# genius_sch.net
KiCad netlist of a schematic drawn in Altium Designer
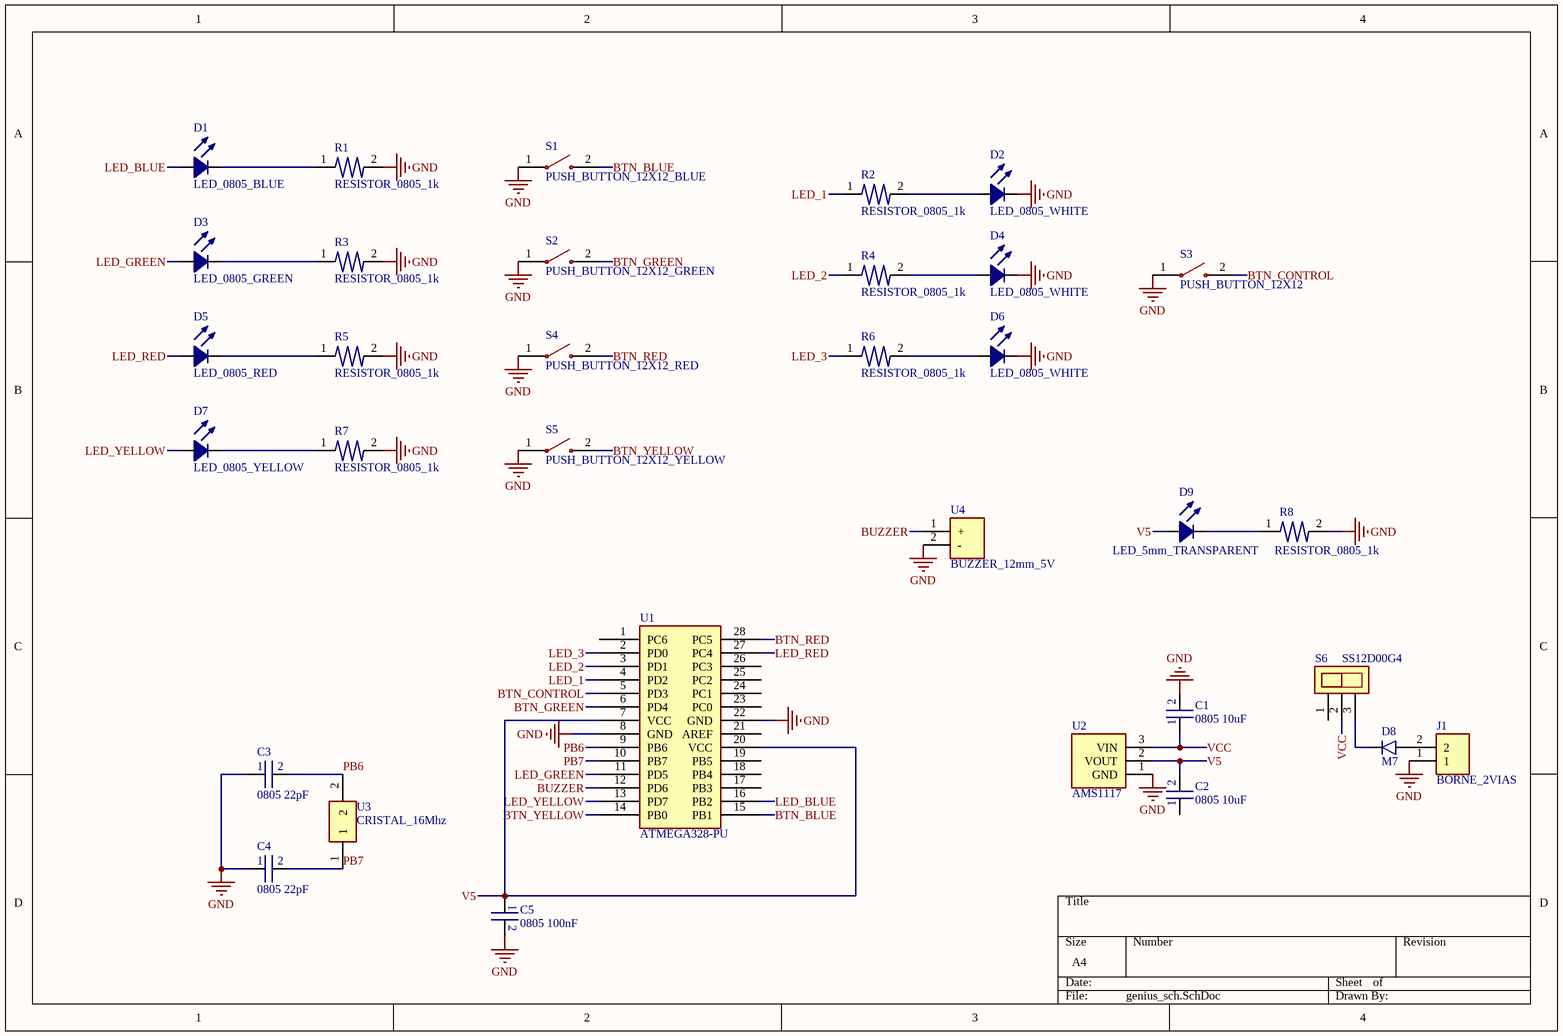
[diagram p0: genius_sch.SchDoc]

(export (version "E")
  (design (tool "Eeschema 10.0.6"))
  (components
    (comp (ref "C1")
      (value "0805 10uF")
      (footprint "CAPACITOR 0805")
      (libsource (lib "Capacitor Ceramico") (part "CAPACITOR 0805"))
    )
    (comp (ref "C2")
      (value "0805 10uF")
      (footprint "CAPACITOR 0805")
      (libsource (lib "Capacitor Ceramico") (part "CAPACITOR 0805"))
    )
    (comp (ref "C3")
      (value "0805 22pF")
      (footprint "CAPACITOR 0805")
      (libsource (lib "Capacitor Ceramico") (part "CAPACITOR 0805"))
    )
    (comp (ref "C4")
      (value "0805 22pF")
      (footprint "CAPACITOR 0805")
      (libsource (lib "Capacitor Ceramico") (part "CAPACITOR 0805"))
    )
    (comp (ref "C5")
      (value "0805 100nF")
      (footprint "CAPACITOR 0805")
      (libsource (lib "Capacitor Ceramico") (part "CAPACITOR 0805"))
    )
    (comp (ref "D1")
      (value "LED_0805_BLUE")
      (footprint "LED_0805_BLUE")
      (libsource (lib "LED") (part "LED_0805_BLUE"))
    )
    (comp (ref "D2")
      (value "LED_0805_WHITE")
      (footprint "LED_0805_WHITE")
      (libsource (lib "LED") (part "LED_0805_WHITE"))
    )
    (comp (ref "D3")
      (value "LED_0805_GREEN")
      (footprint "LED_0805_GREEN")
      (libsource (lib "LED") (part "LED_0805_GREEN"))
    )
    (comp (ref "D4")
      (value "LED_0805_WHITE")
      (footprint "LED_0805_WHITE")
      (libsource (lib "LED") (part "LED_0805_WHITE"))
    )
    (comp (ref "D5")
      (value "LED_0805_RED")
      (footprint "LED_0805_RED")
      (libsource (lib "LED") (part "LED_0805_RED"))
    )
    (comp (ref "D6")
      (value "LED_0805_WHITE")
      (footprint "LED_0805_WHITE")
      (libsource (lib "LED") (part "LED_0805_WHITE"))
    )
    (comp (ref "D7")
      (value "LED_0805_YELLOW")
      (footprint "LED_0805_YELLOW")
      (libsource (lib "LED") (part "LED_0805_YELLOW"))
    )
    (comp (ref "D8") (value "M7") (footprint "M7") (libsource (lib "Diode") (part "M7")))
    (comp (ref "D9")
      (value "LED_5mm_TRANSPARENT")
      (footprint "LED_5mm_TRANSPARENT")
      (libsource (lib "LED") (part "LED_5mm_TRANSPARENT"))
    )
    (comp (ref "J1")
      (value "BORNE_2VIAS")
      (footprint "BORNE_2VIAS")
      (libsource (lib "Connectors") (part "BORNE_2VIAS"))
    )
    (comp (ref "R1")
      (value "RESISTOR_0805_1k")
      (footprint "RESISTOR_0805_1k")
      (libsource (lib "Resistors") (part "RESISTOR_0805_1k"))
    )
    (comp (ref "R2")
      (value "RESISTOR_0805_1k")
      (footprint "RESISTOR_0805_1k")
      (libsource (lib "Resistors") (part "RESISTOR_0805_1k"))
    )
    (comp (ref "R3")
      (value "RESISTOR_0805_1k")
      (footprint "RESISTOR_0805_1k")
      (libsource (lib "Resistors") (part "RESISTOR_0805_1k"))
    )
    (comp (ref "R4")
      (value "RESISTOR_0805_1k")
      (footprint "RESISTOR_0805_1k")
      (libsource (lib "Resistors") (part "RESISTOR_0805_1k"))
    )
    (comp (ref "R5")
      (value "RESISTOR_0805_1k")
      (footprint "RESISTOR_0805_1k")
      (libsource (lib "Resistors") (part "RESISTOR_0805_1k"))
    )
    (comp (ref "R6")
      (value "RESISTOR_0805_1k")
      (footprint "RESISTOR_0805_1k")
      (libsource (lib "Resistors") (part "RESISTOR_0805_1k"))
    )
    (comp (ref "R7")
      (value "RESISTOR_0805_1k")
      (footprint "RESISTOR_0805_1k")
      (libsource (lib "Resistors") (part "RESISTOR_0805_1k"))
    )
    (comp (ref "R8")
      (value "RESISTOR_0805_1k")
      (footprint "RESISTOR_0805_1k")
      (libsource (lib "Resistors") (part "RESISTOR_0805_1k"))
    )
    (comp (ref "S1")
      (value "PUSH_BUTTON_12X12_BLUE")
      (footprint "PUSH_BUTTON_12X12_BLUE")
      (libsource (lib "Buttons & Switches") (part "PUSH_BUTTON_12X12"))
    )
    (comp (ref "S2")
      (value "PUSH_BUTTON_12X12_GREEN")
      (footprint "PUSH_BUTTON_12X12_GREEN")
      (libsource (lib "Buttons & Switches") (part "PUSH_BUTTON_12X12"))
    )
    (comp (ref "S3")
      (value "PUSH_BUTTON_12X12")
      (footprint "PUSH_BUTTON_12X12_WHITE")
      (libsource (lib "Buttons & Switches") (part "PUSH_BUTTON_12X12"))
    )
    (comp (ref "S4")
      (value "PUSH_BUTTON_12X12_RED")
      (footprint "PUSH_BUTTON_12X12_RED")
      (libsource (lib "Buttons & Switches") (part "PUSH_BUTTON_12X12"))
    )
    (comp (ref "S5")
      (value "PUSH_BUTTON_12X12_YELLOW")
      (footprint "PUSH_BUTTON_12X12_YELLOW")
      (libsource (lib "Buttons & Switches") (part "PUSH_BUTTON_12X12"))
    )
    (comp (ref "S6")
      (value "SS12D00G4")
      (footprint "SS12D00G4")
      (libsource (lib "Buttons & Switches") (part "SS12D00G4"))
    )
    (comp (ref "U1")
      (value "ATMEGA328-PU")
      (footprint "ATMEGA328-PU")
      (libsource (lib "Arduino") (part "ATMEGA328-PU"))
    )
    (comp (ref "U2")
      (value "AMS1117")
      (footprint "AMS1117")
      (libsource (lib "Voltage Regulators") (part "AMS1117"))
    )
    (comp (ref "U3")
      (value "CRISTAL_16Mhz")
      (footprint "CRISTAL_16Mhz")
      (libsource (lib "Random") (part "CRISTAL_16Mhz"))
    )
    (comp (ref "U4")
      (value "BUZZER_12mm_5V")
      (footprint "BUZZER_12mm_5V")
      (libsource (lib "Random") (part "BUZZER_12mm_5V"))
    )
  )
  (nets
    (net (code "2") (name "/BTN_BLUE") (class "Default")
      (node (ref "S1") (pin "2") (pinfunction "2_2") (pintype "passive"))
      (node (ref "U1") (pin "15") (pinfunction "PB1_15") (pintype "passive"))
    )
    (net (code "3") (name "/BTN_CONTROL") (class "Default")
      (node (ref "S3") (pin "2") (pinfunction "2_2") (pintype "passive"))
      (node (ref "U1") (pin "5") (pinfunction "PD3_5") (pintype "passive"))
    )
    (net (code "4") (name "/BTN_GREEN") (class "Default")
      (node (ref "S2") (pin "2") (pinfunction "2_2") (pintype "passive"))
      (node (ref "U1") (pin "6") (pinfunction "PD4_6") (pintype "passive"))
    )
    (net (code "5") (name "/BTN_RED") (class "Default")
      (node (ref "S4") (pin "2") (pinfunction "2_2") (pintype "passive"))
      (node (ref "U1") (pin "28") (pinfunction "PC5_28") (pintype "passive"))
    )
    (net (code "6") (name "/BTN_YELLOW") (class "Default")
      (node (ref "S5") (pin "2") (pinfunction "2_2") (pintype "passive"))
      (node (ref "U1") (pin "14") (pinfunction "PB0_14") (pintype "passive"))
    )
    (net (code "7") (name "/BUZZER") (class "Default")
      (node (ref "U1") (pin "12") (pinfunction "PD6_12") (pintype "passive"))
      (node (ref "U4") (pin "1") (pinfunction "+_1") (pintype "passive"))
    )
    (net (code "8") (name "/LED_1") (class "Default")
      (node (ref "R2") (pin "1") (pinfunction "1_1") (pintype "passive"))
      (node (ref "U1") (pin "4") (pinfunction "PD2_4") (pintype "passive"))
    )
    (net (code "9") (name "/LED_2") (class "Default")
      (node (ref "R4") (pin "1") (pinfunction "1_1") (pintype "passive"))
      (node (ref "U1") (pin "3") (pinfunction "PD1_3") (pintype "passive"))
    )
    (net (code "10") (name "/LED_3") (class "Default")
      (node (ref "R6") (pin "1") (pinfunction "1_1") (pintype "passive"))
      (node (ref "U1") (pin "2") (pinfunction "PD0_2") (pintype "passive"))
    )
    (net (code "11") (name "/LED_BLUE") (class "Default")
      (node (ref "D1") (pin "1") (pinfunction "1_1") (pintype "passive"))
      (node (ref "U1") (pin "16") (pinfunction "PB2_16") (pintype "passive"))
    )
    (net (code "12") (name "/LED_GREEN") (class "Default")
      (node (ref "D3") (pin "1") (pinfunction "1_1") (pintype "passive"))
      (node (ref "U1") (pin "11") (pinfunction "PD5_11") (pintype "passive"))
    )
    (net (code "13") (name "/LED_RED") (class "Default")
      (node (ref "D5") (pin "1") (pinfunction "1_1") (pintype "passive"))
      (node (ref "U1") (pin "27") (pinfunction "PC4_27") (pintype "passive"))
    )
    (net (code "14") (name "/LED_YELLOW") (class "Default")
      (node (ref "D7") (pin "1") (pinfunction "1_1") (pintype "passive"))
      (node (ref "U1") (pin "13") (pinfunction "PD7_13") (pintype "passive"))
    )
    (net (code "15") (name "/PB6") (class "Default")
      (node (ref "C3") (pin "2") (pinfunction "2_2") (pintype "passive"))
      (node (ref "U1") (pin "9") (pinfunction "PB6_9") (pintype "passive"))
      (node (ref "U3") (pin "2") (pinfunction "2_2") (pintype "passive"))
    )
    (net (code "16") (name "/PB7") (class "Default")
      (node (ref "C4") (pin "2") (pinfunction "2_2") (pintype "passive"))
      (node (ref "U1") (pin "10") (pinfunction "PB7_10") (pintype "passive"))
      (node (ref "U3") (pin "1") (pinfunction "1_1") (pintype "passive"))
    )
    (net (code "17") (name "/V5") (class "Default")
      (node (ref "C2") (pin "2") (pinfunction "2_2") (pintype "passive"))
      (node (ref "C5") (pin "1") (pinfunction "1_1") (pintype "passive"))
      (node (ref "D9") (pin "1") (pinfunction "1_1") (pintype "passive"))
      (node (ref "U1") (pin "20") (pinfunction "VCC_20") (pintype "passive"))
      (node (ref "U1") (pin "7") (pinfunction "VCC_7") (pintype "passive"))
      (node (ref "U2") (pin "2") (pinfunction "VOUT_2") (pintype "passive"))
    )
    (net (code "18") (name "/VCC") (class "Default")
      (node (ref "C1") (pin "1") (pinfunction "1_1") (pintype "passive"))
      (node (ref "S6") (pin "2") (pintype "passive"))
      (node (ref "U2") (pin "3") (pinfunction "VIN_3") (pintype "passive"))
    )
    (net (code "19") (name "GND") (class "Default")
      (node (ref "C1") (pin "2") (pinfunction "2_2") (pintype "passive"))
      (node (ref "C3") (pin "1") (pinfunction "1_1") (pintype "passive"))
      (node (ref "C4") (pin "1") (pinfunction "1_1") (pintype "passive"))
      (node (ref "C5") (pin "2") (pinfunction "2_2") (pintype "passive"))
      (node (ref "D2") (pin "2") (pinfunction "2_2") (pintype "passive"))
      (node (ref "D4") (pin "2") (pinfunction "2_2") (pintype "passive"))
      (node (ref "D6") (pin "2") (pinfunction "2_2") (pintype "passive"))
      (node (ref "J1") (pin "1") (pinfunction "1_1") (pintype "passive"))
      (node (ref "R1") (pin "2") (pinfunction "2_2") (pintype "passive"))
      (node (ref "R3") (pin "2") (pinfunction "2_2") (pintype "passive"))
      (node (ref "R5") (pin "2") (pinfunction "2_2") (pintype "passive"))
      (node (ref "R7") (pin "2") (pinfunction "2_2") (pintype "passive"))
      (node (ref "R8") (pin "2") (pinfunction "2_2") (pintype "passive"))
      (node (ref "S1") (pin "1") (pinfunction "1_1") (pintype "passive"))
      (node (ref "S2") (pin "1") (pinfunction "1_1") (pintype "passive"))
      (node (ref "S3") (pin "1") (pinfunction "1_1") (pintype "passive"))
      (node (ref "S4") (pin "1") (pinfunction "1_1") (pintype "passive"))
      (node (ref "S5") (pin "1") (pinfunction "1_1") (pintype "passive"))
      (node (ref "U1") (pin "22") (pinfunction "GND_22") (pintype "passive"))
      (node (ref "U1") (pin "8") (pinfunction "GND_8") (pintype "passive"))
      (node (ref "U2") (pin "1") (pinfunction "GND_1") (pintype "passive"))
      (node (ref "U4") (pin "2") (pinfunction "-_2") (pintype "passive"))
    )
    (net (code "20") (name "Net-(D1-Pad2)") (class "Default")
      (node (ref "D1") (pin "2") (pinfunction "2_2") (pintype "passive"))
      (node (ref "R1") (pin "1") (pinfunction "1_1") (pintype "passive"))
    )
    (net (code "21") (name "Net-(D2-Pad1)") (class "Default")
      (node (ref "D2") (pin "1") (pinfunction "1_1") (pintype "passive"))
      (node (ref "R2") (pin "2") (pinfunction "2_2") (pintype "passive"))
    )
    (net (code "22") (name "Net-(D3-Pad2)") (class "Default")
      (node (ref "D3") (pin "2") (pinfunction "2_2") (pintype "passive"))
      (node (ref "R3") (pin "1") (pinfunction "1_1") (pintype "passive"))
    )
    (net (code "23") (name "Net-(D4-Pad1)") (class "Default")
      (node (ref "D4") (pin "1") (pinfunction "1_1") (pintype "passive"))
      (node (ref "R4") (pin "2") (pinfunction "2_2") (pintype "passive"))
    )
    (net (code "24") (name "Net-(D5-Pad2)") (class "Default")
      (node (ref "D5") (pin "2") (pinfunction "2_2") (pintype "passive"))
      (node (ref "R5") (pin "1") (pinfunction "1_1") (pintype "passive"))
    )
    (net (code "25") (name "Net-(D6-Pad1)") (class "Default")
      (node (ref "D6") (pin "1") (pinfunction "1_1") (pintype "passive"))
      (node (ref "R6") (pin "2") (pinfunction "2_2") (pintype "passive"))
    )
    (net (code "26") (name "Net-(D7-Pad2)") (class "Default")
      (node (ref "D7") (pin "2") (pinfunction "2_2") (pintype "passive"))
      (node (ref "R7") (pin "1") (pinfunction "1_1") (pintype "passive"))
    )
    (net (code "27") (name "Net-(D8-Pad1)") (class "Default")
      (node (ref "D8") (pin "1") (pinfunction "1_1") (pintype "passive"))
      (node (ref "J1") (pin "2") (pinfunction "2_2") (pintype "passive"))
    )
    (net (code "28") (name "Net-(D8-Pad2)") (class "Default")
      (node (ref "D8") (pin "2") (pintype "passive"))
      (node (ref "S6") (pin "3") (pintype "passive"))
    )
    (net (code "29") (name "Net-(D9-Pad2)") (class "Default")
      (node (ref "D9") (pin "2") (pinfunction "2_2") (pintype "passive"))
      (node (ref "R8") (pin "1") (pinfunction "1_1") (pintype "passive"))
    )
    (net (code "30") (name "unconnected-(C2-Pad1)") (class "Default")
      (node (ref "C2") (pin "1") (pinfunction "1_1") (pintype "passive"))
    )
    (net (code "31") (name "unconnected-(S6-Pad1)") (class "Default")
      (node (ref "S6") (pin "1") (pintype "passive"))
    )
    (net (code "32") (name "unconnected-(U1-AREF-Pad21)") (class "Default")
      (node (ref "U1") (pin "21") (pinfunction "AREF_21") (pintype "passive"))
    )
    (net (code "33") (name "unconnected-(U1-PB3-Pad17)") (class "Default")
      (node (ref "U1") (pin "17") (pinfunction "PB3_17") (pintype "passive"))
    )
    (net (code "34") (name "unconnected-(U1-PB4-Pad18)") (class "Default")
      (node (ref "U1") (pin "18") (pinfunction "PB4_18") (pintype "passive"))
    )
    (net (code "35") (name "unconnected-(U1-PB5-Pad19)") (class "Default")
      (node (ref "U1") (pin "19") (pinfunction "PB5_19") (pintype "passive"))
    )
    (net (code "36") (name "unconnected-(U1-PC0-Pad23)") (class "Default")
      (node (ref "U1") (pin "23") (pinfunction "PC0_23") (pintype "passive"))
    )
    (net (code "37") (name "unconnected-(U1-PC1-Pad24)") (class "Default")
      (node (ref "U1") (pin "24") (pinfunction "PC1_24") (pintype "passive"))
    )
    (net (code "38") (name "unconnected-(U1-PC2-Pad25)") (class "Default")
      (node (ref "U1") (pin "25") (pinfunction "PC2_25") (pintype "passive"))
    )
    (net (code "39") (name "unconnected-(U1-PC3-Pad26)") (class "Default")
      (node (ref "U1") (pin "26") (pinfunction "PC3_26") (pintype "passive"))
    )
    (net (code "40") (name "unconnected-(U1-PC6-Pad1)") (class "Default")
      (node (ref "U1") (pin "1") (pinfunction "PC6_1") (pintype "passive"))
    )
  )
)
